# PDM-S01-V00-PDMCConnector.net
KiCad netlist of a schematic drawn in Altium Designer
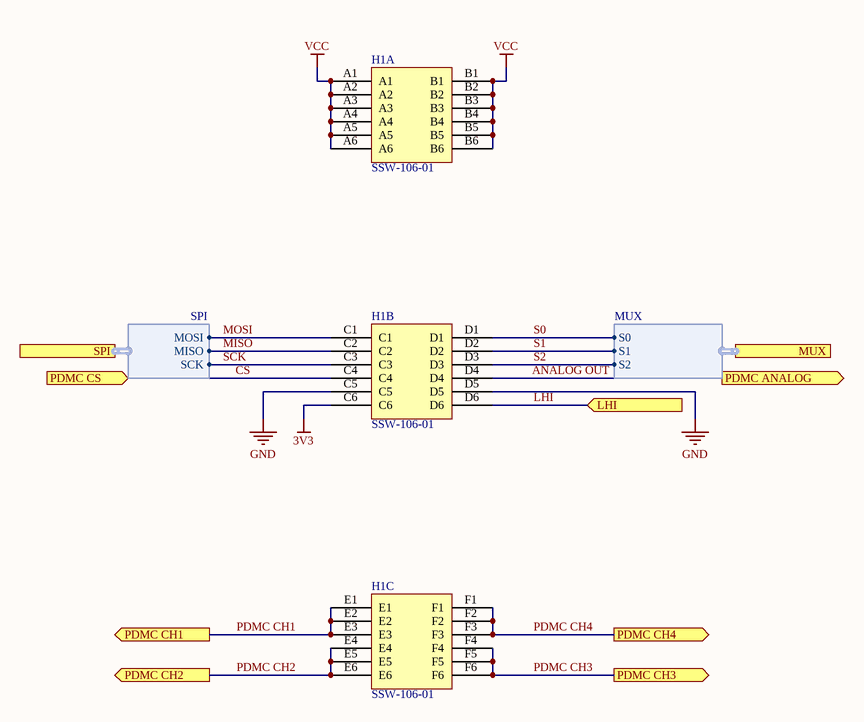
[diagram p0: PDM-S01-V00-PDMCConnector.SchDoc]

(export (version "E")
  (design (tool "Eeschema 10.0.6"))
  (components
    (comp (ref "H1")
      (value "SSW-106-01")
      (footprint "SSW-106-01")
      (description "CONN RCPT 12POS 0.1 TIN PCB")
      (libsource (lib "SamtecHeader") (part "SSW-106-01"))
    )
  )
  (nets
    (net (code "3") (name "/ANALOG OUT") (class "Default")
      (node (ref "H1") (pin "D4") (pinfunction "D4_D4") (pintype "passive"))
    )
    (net (code "4") (name "/CS") (class "Default")
      (node (ref "H1") (pin "C4") (pinfunction "C4_C4") (pintype "passive"))
    )
    (net (code "5") (name "/LHI") (class "Default")
      (node (ref "H1") (pin "D6") (pinfunction "D6_D6") (pintype "passive"))
    )
    (net (code "6") (name "/MISO") (class "Default")
      (node (ref "H1") (pin "C2") (pinfunction "C2_C2") (pintype "passive"))
    )
    (net (code "7") (name "/MOSI") (class "Default")
      (node (ref "H1") (pin "C1") (pinfunction "C1_C1") (pintype "passive"))
    )
    (net (code "8") (name "/PDMC CH1") (class "Default")
      (node (ref "H1") (pin "E1") (pinfunction "E1_E1") (pintype "passive"))
      (node (ref "H1") (pin "E2") (pinfunction "E2_E2") (pintype "passive"))
      (node (ref "H1") (pin "E3") (pinfunction "E3_E3") (pintype "passive"))
    )
    (net (code "9") (name "/PDMC CH2") (class "Default")
      (node (ref "H1") (pin "E4") (pinfunction "E4_E4") (pintype "passive"))
      (node (ref "H1") (pin "E5") (pinfunction "E5_E5") (pintype "passive"))
      (node (ref "H1") (pin "E6") (pinfunction "E6_E6") (pintype "passive"))
    )
    (net (code "10") (name "/PDMC CH3") (class "Default")
      (node (ref "H1") (pin "F4") (pinfunction "F4_F4") (pintype "passive"))
      (node (ref "H1") (pin "F5") (pinfunction "F5_F5") (pintype "passive"))
      (node (ref "H1") (pin "F6") (pinfunction "F6_F6") (pintype "passive"))
    )
    (net (code "11") (name "/PDMC CH4") (class "Default")
      (node (ref "H1") (pin "F1") (pinfunction "F1_F1") (pintype "passive"))
      (node (ref "H1") (pin "F2") (pinfunction "F2_F2") (pintype "passive"))
      (node (ref "H1") (pin "F3") (pinfunction "F3_F3") (pintype "passive"))
    )
    (net (code "12") (name "/S0") (class "Default")
      (node (ref "H1") (pin "D1") (pinfunction "D1_D1") (pintype "passive"))
    )
    (net (code "13") (name "/S1") (class "Default")
      (node (ref "H1") (pin "D2") (pinfunction "D2_D2") (pintype "passive"))
    )
    (net (code "14") (name "/S2") (class "Default")
      (node (ref "H1") (pin "D3") (pinfunction "D3_D3") (pintype "passive"))
    )
    (net (code "15") (name "/SCK") (class "Default")
      (node (ref "H1") (pin "C3") (pinfunction "C3_C3") (pintype "passive"))
    )
    (net (code "18") (name "3V3") (class "Default")
      (node (ref "H1") (pin "C6") (pinfunction "C6_C6") (pintype "passive"))
    )
    (net (code "19") (name "GND") (class "Default")
      (node (ref "H1") (pin "C5") (pinfunction "C5_C5") (pintype "passive"))
      (node (ref "H1") (pin "D5") (pinfunction "D5_D5") (pintype "passive"))
    )
    (net (code "20") (name "VCC") (class "Default")
      (node (ref "H1") (pin "A1") (pinfunction "A1_A1") (pintype "passive"))
      (node (ref "H1") (pin "A2") (pinfunction "A2_A2") (pintype "passive"))
      (node (ref "H1") (pin "A3") (pinfunction "A3_A3") (pintype "passive"))
      (node (ref "H1") (pin "A4") (pinfunction "A4_A4") (pintype "passive"))
      (node (ref "H1") (pin "A5") (pinfunction "A5_A5") (pintype "passive"))
      (node (ref "H1") (pin "A6") (pinfunction "A6_A6") (pintype "passive"))
      (node (ref "H1") (pin "B1") (pinfunction "B1_B1") (pintype "passive"))
      (node (ref "H1") (pin "B2") (pinfunction "B2_B2") (pintype "passive"))
      (node (ref "H1") (pin "B3") (pinfunction "B3_B3") (pintype "passive"))
      (node (ref "H1") (pin "B4") (pinfunction "B4_B4") (pintype "passive"))
      (node (ref "H1") (pin "B5") (pinfunction "B5_B5") (pintype "passive"))
      (node (ref "H1") (pin "B6") (pinfunction "B6_B6") (pintype "passive"))
    )
  )
)
